# Sheet2.net
KiCad netlist of a schematic drawn in Altium Designer
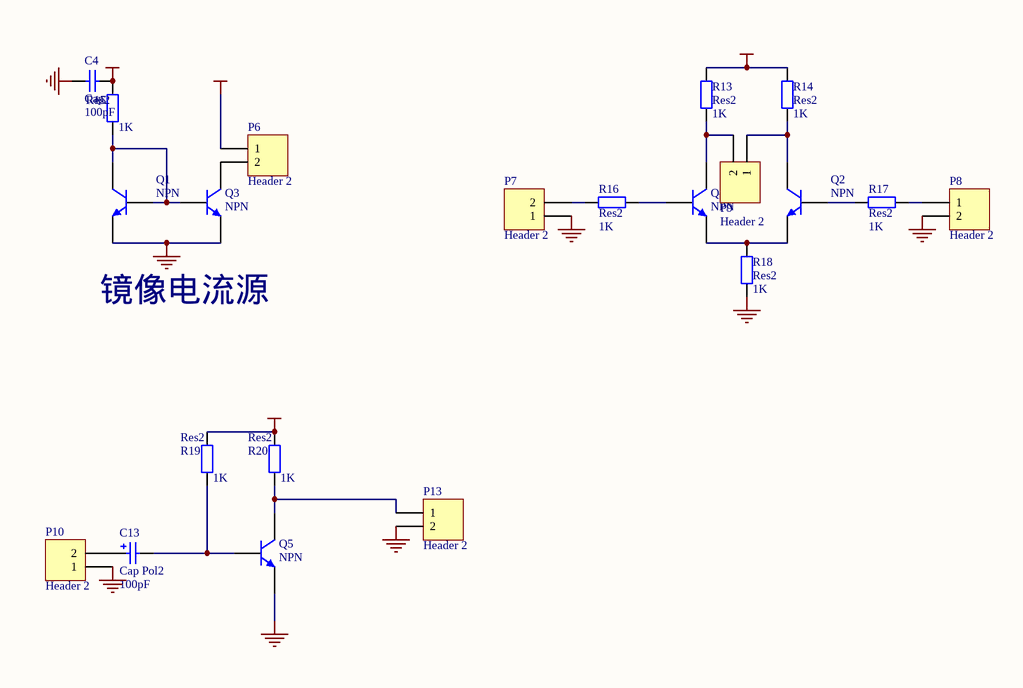
[diagram p0: Sheet2.SchDoc]

(export (version "E")
  (design (tool "Eeschema 10.0.6"))
  (components
    (comp (ref "C4")
      (value "Cap")
      (footprint "6-0805")
      (description "Capacitor")
      (fields (field (name "ALTIUM_VALUE") "100pF") (field (name "PUBLISHER") "Altium Limited"))
      (libsource (lib "Miscellaneous Devices") (part "Cap"))
    )
    (comp (ref "C13")
      (value "Cap Pol2")
      (footprint "3.2X1.6X1.1")
      (description "Polarized Capacitor (Axial)")
      (fields (field (name "ALTIUM_VALUE") "100pF") (field (name "PUBLISHER") "Altium Limited"))
      (libsource (lib "Miscellaneous Devices") (part "Cap Pol2"))
    )
    (comp (ref "P6")
      (value "Header 2")
      (footprint "HDR1X2")
      (description "Header, 2-Pin")
      (fields (field (name "PUBLISHER") "Altium Limited"))
      (libsource (lib "") (part "Header 2_1"))
    )
    (comp (ref "P7")
      (value "Header 2")
      (footprint "HDR1X2")
      (description "Header, 2-Pin")
      (fields (field (name "PUBLISHER") "Altium Limited"))
      (libsource (lib "Miscellaneous Connectors") (part "Header 2"))
    )
    (comp (ref "P8")
      (value "Header 2")
      (footprint "HDR1X2")
      (description "Header, 2-Pin")
      (fields (field (name "PUBLISHER") "Altium Limited"))
      (libsource (lib "") (part "Header 2_1"))
    )
    (comp (ref "P9")
      (value "Header 2")
      (footprint "HDR1X2")
      (description "Header, 2-Pin")
      (fields (field (name "PUBLISHER") "Altium Limited"))
      (libsource (lib "") (part "Header 2_2"))
    )
    (comp (ref "P10")
      (value "Header 2")
      (footprint "HDR1X2")
      (description "Header, 2-Pin")
      (fields (field (name "PUBLISHER") "Altium Limited"))
      (libsource (lib "Miscellaneous Connectors") (part "Header 2"))
    )
    (comp (ref "P13")
      (value "Header 2")
      (footprint "HDR1X2")
      (description "Header, 2-Pin")
      (fields (field (name "PUBLISHER") "Altium Limited"))
      (libsource (lib "") (part "Header 2_1"))
    )
    (comp (ref "Q1")
      (value "NPN")
      (footprint "TO-226")
      (description "NPN Bipolar Transistor")
      (fields (field (name "PUBLISHER") "Altium Limited"))
      (libsource (lib "Miscellaneous Devices") (part "NPN"))
    )
    (comp (ref "Q2")
      (value "NPN")
      (footprint "TO-226")
      (description "NPN Bipolar Transistor")
      (fields (field (name "PUBLISHER") "Altium Limited"))
      (libsource (lib "Miscellaneous Devices") (part "NPN"))
    )
    (comp (ref "Q3")
      (value "NPN")
      (footprint "TO-226")
      (description "NPN Bipolar Transistor")
      (fields (field (name "PUBLISHER") "Altium Limited"))
      (libsource (lib "Miscellaneous Devices") (part "NPN"))
    )
    (comp (ref "Q4")
      (value "NPN")
      (footprint "TO-226")
      (description "NPN Bipolar Transistor")
      (fields (field (name "PUBLISHER") "Altium Limited"))
      (libsource (lib "Miscellaneous Devices") (part "NPN"))
    )
    (comp (ref "Q5")
      (value "NPN")
      (footprint "TO-226")
      (description "NPN Bipolar Transistor")
      (fields (field (name "PUBLISHER") "Altium Limited"))
      (libsource (lib "Miscellaneous Devices") (part "NPN"))
    )
    (comp (ref "R13")
      (value "Res2")
      (footprint "6-0805")
      (description "Resistor")
      (fields (field (name "ALTIUM_VALUE") "1K") (field (name "PUBLISHER") "Altium Limited"))
      (libsource (lib "Miscellaneous Devices") (part "6-0805"))
    )
    (comp (ref "R14")
      (value "Res2")
      (footprint "6-0805")
      (description "Resistor")
      (fields (field (name "ALTIUM_VALUE") "1K") (field (name "PUBLISHER") "Altium Limited"))
      (libsource (lib "Miscellaneous Devices") (part "6-0805"))
    )
    (comp (ref "R15")
      (value "Res2")
      (footprint "6-0805")
      (description "Resistor")
      (fields (field (name "ALTIUM_VALUE") "1K") (field (name "PUBLISHER") "Altium Limited"))
      (libsource (lib "") (part "6-0805_1"))
    )
    (comp (ref "R16")
      (value "Res2")
      (footprint "6-0805")
      (description "Resistor")
      (fields (field (name "ALTIUM_VALUE") "1K") (field (name "PUBLISHER") "Altium Limited"))
      (libsource (lib "") (part "6-0805_2"))
    )
    (comp (ref "R17")
      (value "Res2")
      (footprint "6-0805")
      (description "Resistor")
      (fields (field (name "ALTIUM_VALUE") "1K") (field (name "PUBLISHER") "Altium Limited"))
      (libsource (lib "") (part "6-0805_2"))
    )
    (comp (ref "R18")
      (value "Res2")
      (footprint "6-0805")
      (description "Resistor")
      (fields (field (name "ALTIUM_VALUE") "1K") (field (name "PUBLISHER") "Altium Limited"))
      (libsource (lib "Miscellaneous Devices") (part "6-0805"))
    )
    (comp (ref "R19")
      (value "Res2")
      (footprint "6-0805")
      (description "Resistor")
      (fields (field (name "ALTIUM_VALUE") "1K") (field (name "PUBLISHER") "Altium Limited"))
      (libsource (lib "") (part "6-0805_1"))
    )
    (comp (ref "R20")
      (value "Res2")
      (footprint "6-0805")
      (description "Resistor")
      (fields (field (name "ALTIUM_VALUE") "1K") (field (name "PUBLISHER") "Altium Limited"))
      (libsource (lib "") (part "6-0805_1"))
    )
  )
  (nets
    (net (code "1") (name "+12") (class "Default")
      (node (ref "C4") (pin "2") (pinfunction "2_2") (pintype "passive"))
      (node (ref "P6") (pin "1") (pinfunction "1_1") (pintype "passive"))
      (node (ref "R13") (pin "1") (pinfunction "1_1") (pintype "passive"))
      (node (ref "R14") (pin "1") (pinfunction "1_1") (pintype "passive"))
      (node (ref "R15") (pin "2") (pinfunction "2_2") (pintype "passive"))
      (node (ref "R19") (pin "2") (pinfunction "2_2") (pintype "passive"))
      (node (ref "R20") (pin "2") (pinfunction "2_2") (pintype "passive"))
    )
    (net (code "2") (name "GND") (class "Default")
      (node (ref "C4") (pin "1") (pinfunction "1_1") (pintype "passive"))
      (node (ref "P10") (pin "1") (pinfunction "1_1") (pintype "passive"))
      (node (ref "P13") (pin "2") (pinfunction "2_2") (pintype "passive"))
      (node (ref "P7") (pin "1") (pinfunction "1_1") (pintype "passive"))
      (node (ref "P8") (pin "2") (pinfunction "2_2") (pintype "passive"))
      (node (ref "Q1") (pin "3") (pinfunction "E_3") (pintype "passive"))
      (node (ref "Q3") (pin "3") (pinfunction "E_3") (pintype "passive"))
      (node (ref "Q5") (pin "3") (pinfunction "E_3") (pintype "passive"))
      (node (ref "R18") (pin "2") (pinfunction "2_2") (pintype "passive"))
    )
    (net (code "3") (name "Net-(C13-Pad1)") (class "Default")
      (node (ref "C13") (pin "1") (pinfunction "1_1") (pintype "passive"))
      (node (ref "P10") (pin "2") (pinfunction "2_2") (pintype "passive"))
    )
    (net (code "4") (name "Net-(P7-Pad2)") (class "Default")
      (node (ref "P7") (pin "2") (pinfunction "2_2") (pintype "passive"))
      (node (ref "R16") (pin "2") (pinfunction "2_2") (pintype "passive"))
    )
    (net (code "5") (name "Net-(P8-Pad1)") (class "Default")
      (node (ref "P8") (pin "1") (pinfunction "1_1") (pintype "passive"))
      (node (ref "R17") (pin "1") (pinfunction "1_1") (pintype "passive"))
    )
    (net (code "6") (name "Net-(Q1-B)") (class "Default")
      (node (ref "Q1") (pin "1") (pinfunction "C_1") (pintype "passive"))
      (node (ref "Q1") (pin "2") (pinfunction "B_2") (pintype "passive"))
      (node (ref "Q3") (pin "2") (pinfunction "B_2") (pintype "passive"))
      (node (ref "R15") (pin "1") (pinfunction "1_1") (pintype "passive"))
    )
    (net (code "7") (name "Net-(Q2-B)") (class "Default")
      (node (ref "Q2") (pin "2") (pinfunction "B_2") (pintype "passive"))
      (node (ref "R17") (pin "2") (pinfunction "2_2") (pintype "passive"))
    )
    (net (code "8") (name "Net-(Q2-C)") (class "Default")
      (node (ref "P9") (pin "1") (pinfunction "1_1") (pintype "passive"))
      (node (ref "Q2") (pin "1") (pinfunction "C_1") (pintype "passive"))
      (node (ref "R14") (pin "2") (pinfunction "2_2") (pintype "passive"))
    )
    (net (code "9") (name "Net-(Q2-E)") (class "Default")
      (node (ref "Q2") (pin "3") (pinfunction "E_3") (pintype "passive"))
      (node (ref "Q4") (pin "3") (pinfunction "E_3") (pintype "passive"))
      (node (ref "R18") (pin "1") (pinfunction "1_1") (pintype "passive"))
    )
    (net (code "10") (name "Net-(Q3-C)") (class "Default")
      (node (ref "P6") (pin "2") (pinfunction "2_2") (pintype "passive"))
      (node (ref "Q3") (pin "1") (pinfunction "C_1") (pintype "passive"))
    )
    (net (code "11") (name "Net-(Q4-B)") (class "Default")
      (node (ref "Q4") (pin "2") (pinfunction "B_2") (pintype "passive"))
      (node (ref "R16") (pin "1") (pinfunction "1_1") (pintype "passive"))
    )
    (net (code "12") (name "Net-(Q4-C)") (class "Default")
      (node (ref "P9") (pin "2") (pinfunction "2_2") (pintype "passive"))
      (node (ref "Q4") (pin "1") (pinfunction "C_1") (pintype "passive"))
      (node (ref "R13") (pin "2") (pinfunction "2_2") (pintype "passive"))
    )
    (net (code "13") (name "Net-(Q5-B)") (class "Default")
      (node (ref "C13") (pin "2") (pinfunction "2_2") (pintype "passive"))
      (node (ref "Q5") (pin "2") (pinfunction "B_2") (pintype "passive"))
      (node (ref "R19") (pin "1") (pinfunction "1_1") (pintype "passive"))
    )
    (net (code "14") (name "Net-(Q5-C)") (class "Default")
      (node (ref "P13") (pin "1") (pinfunction "1_1") (pintype "passive"))
      (node (ref "Q5") (pin "1") (pinfunction "C_1") (pintype "passive"))
      (node (ref "R20") (pin "1") (pinfunction "1_1") (pintype "passive"))
    )
  )
)
